# powersupply.net
KiCad netlist of a schematic drawn in Altium Designer
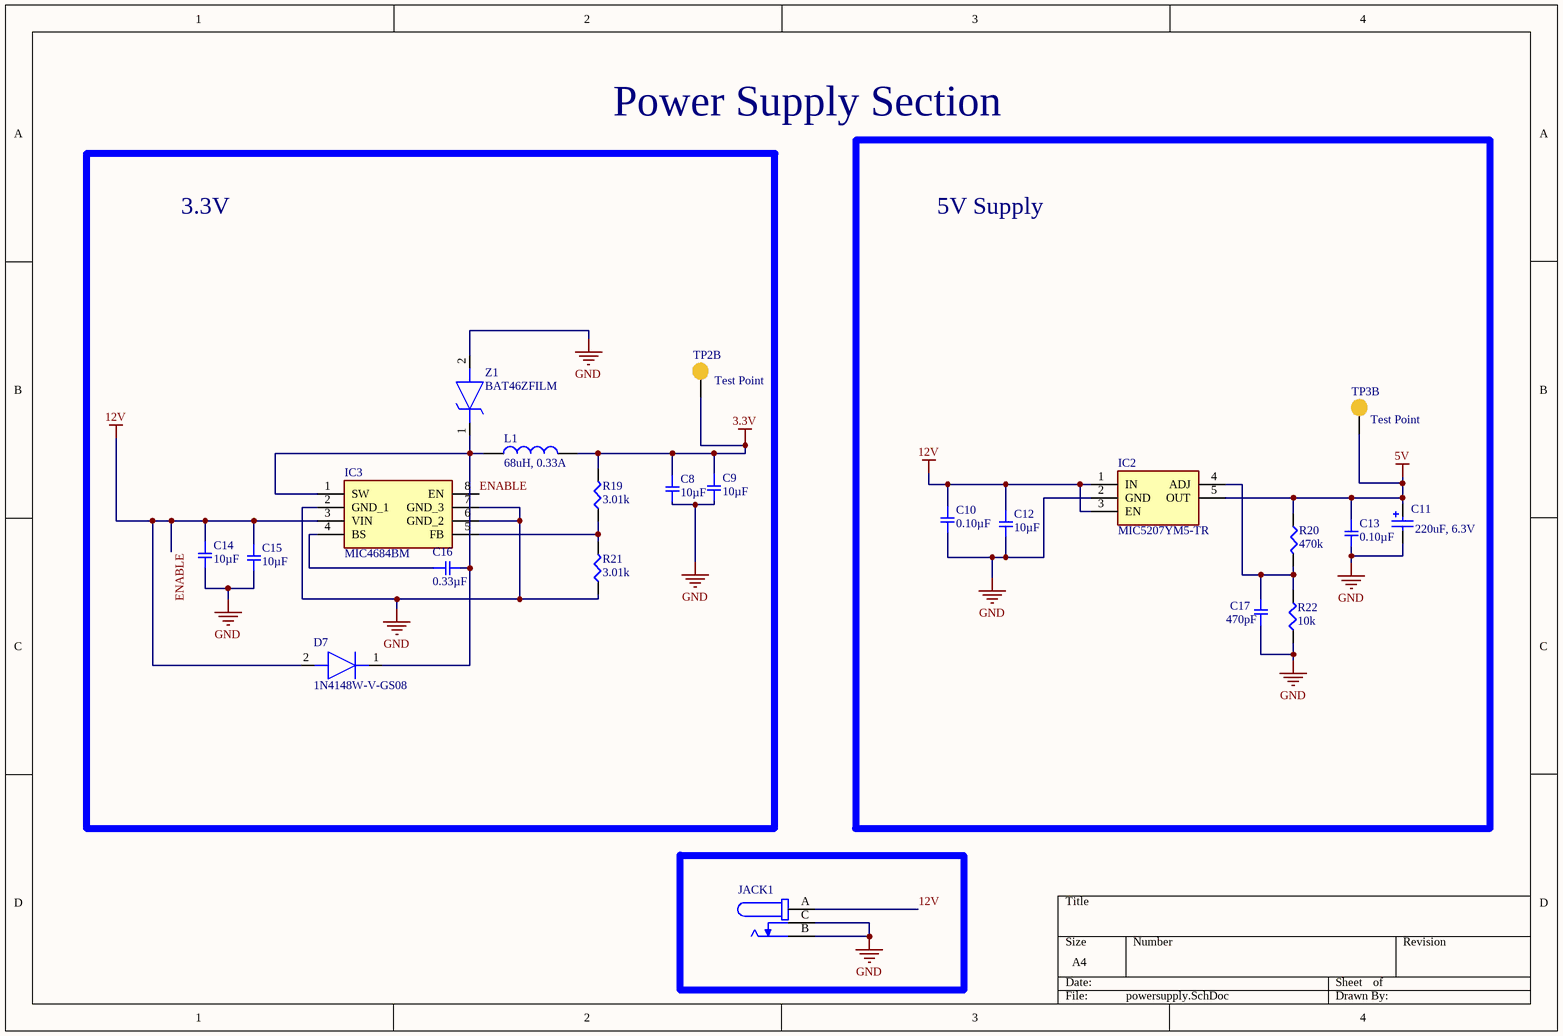
[diagram p0: powersupply.SchDoc]

(export (version "E")
  (design (tool "Eeschema 10.0.6"))
  (components
    (comp (ref "C8")
      (value "10µF")
      (footprint "SMD-0805C")
      (description "CAP CER 10UF 10V X7R 0805")
      (fields
        (field (name "DIGI-KEY PART NUMBER") "490-12646-1-ND")
        (field (name "PART NUMBER") "GCJ21BR71A106KE01L")
      )
      (libsource (lib "capacitor_murata_0805") (part "GCJ21BR71A106KE01L"))
    )
    (comp (ref "C9")
      (value "10µF")
      (footprint "SMD-0805C")
      (description "CAP CER 10UF 10V X7R 0805")
      (fields
        (field (name "DIGI-KEY PART NUMBER") "490-12646-1-ND")
        (field (name "PART NUMBER") "GCJ21BR71A106KE01L")
      )
      (libsource (lib "capacitor_murata_0805") (part "GCJ21BR71A106KE01L"))
    )
    (comp (ref "C10")
      (value "0.10µF")
      (footprint "SMD-0805C")
      (description "CAP CER 0.1UF 50V X7R 0805")
      (fields
        (field (name "DIGI-KEY PART NUMBER") "490-11955-1-ND")
        (field (name "PART NUMBER") "GCD21BR71H104KA01L")
      )
      (libsource (lib "capacitor_murata_0805") (part "GCD21BR71H104KA01L"))
    )
    (comp (ref "C11")
      (value "220uF, 6.3V")
      (footprint "WCAP-ASLI_6.3x5.5")
      (description "WCAP-ASLI SMT Aluminum Electrolytic Capacitors, D6.3mm x L5.5mm, 220uF, +/-20%, 6.3VDC")
      (fields (field (name "PART NUMBER") "865080143009") (field (name "PUBLISHER") "Wurth Elektronik"))
      (libsource (lib "SMD aluminum EL CAPS WCAP-ASLI_rev19a") (part "865080143009"))
    )
    (comp (ref "C12")
      (value "10µF")
      (footprint "SMD-0805C")
      (description "CAP CER 10UF 10V X7R 0805")
      (fields
        (field (name "DIGI-KEY PART NUMBER") "490-12646-1-ND")
        (field (name "PART NUMBER") "GCJ21BR71A106KE01L")
      )
      (libsource (lib "capacitor_murata_0805") (part "GCJ21BR71A106KE01L"))
    )
    (comp (ref "C13")
      (value "0.10µF")
      (footprint "SMD-0805C")
      (description "CAP CER 0.1UF 50V X7R 0805")
      (fields
        (field (name "DIGI-KEY PART NUMBER") "490-11955-1-ND")
        (field (name "PART NUMBER") "GCD21BR71H104KA01L")
      )
      (libsource (lib "capacitor_murata_0805") (part "GCD21BR71H104KA01L"))
    )
    (comp (ref "C14")
      (value "10µF")
      (footprint "SMD-0805C")
      (description "CAP CER 10UF 10V X7R 0805")
      (fields
        (field (name "DIGI-KEY PART NUMBER") "490-12646-1-ND")
        (field (name "PART NUMBER") "GCJ21BR71A106KE01L")
      )
      (libsource (lib "capacitor_murata_0805") (part "GCJ21BR71A106KE01L"))
    )
    (comp (ref "C15")
      (value "10µF")
      (footprint "SMD-0805C")
      (description "CAP CER 10UF 10V X7R 0805")
      (fields
        (field (name "DIGI-KEY PART NUMBER") "490-12646-1-ND")
        (field (name "PART NUMBER") "GCJ21BR71A106KE01L")
      )
      (libsource (lib "capacitor_murata_0805") (part "GCJ21BR71A106KE01L"))
    )
    (comp (ref "C16")
      (value "0.33µF")
      (footprint "SMD-0805C")
      (description "CAP CER 0.33UF 16V X7R 0805")
      (fields
        (field (name "DIGI-KEY PART NUMBER") "490-9752-1-ND")
        (field (name "PART NUMBER") "GRM21BR71C334KA01L")
      )
      (libsource (lib "capacitor_murata_0805") (part "GRM21BR71C334KA01L"))
    )
    (comp (ref "C17")
      (value "470pF")
      (footprint "SMD-0805C")
      (description "CAP CER 470PF 50V NP0 0805")
      (fields
        (field (name "DIGI-KEY PART NUMBER") "490-6056-1-ND")
        (field (name "PART NUMBER") "GCM2165C1H471JA16D")
      )
      (libsource (lib "capacitor_murata_0805") (part "GCM2165C1H471JA16D"))
    )
    (comp (ref "D7")
      (value "1N4148W-V-GS08")
      (footprint "SamacSys:1N4148WVGS08")
      (description "Diode")
      (fields (field (name "MOUSER PART NUMBER") "625-1N4148W-V"))
      (libsource (lib "*") (part "1N4148W-V-GS08"))
    )
    (comp (ref "IC2")
      (value "MIC5207YM5-TR")
      (footprint "SamacSys:SOT95P280X130-5N")
      (description "Integrated Circuit")
      (fields (field (name "MANUFACTURER_PART_NUMBER") "MIC5207"))
      (libsource (lib "*") (part "MIC5207"))
    )
    (comp (ref "IC3")
      (value "MIC4684BM")
      (footprint "SamacSys:SOIC127P602X173-8N")
      (description "Integrated Circuit")
      (libsource (lib "*") (part "MIC4684BM"))
    )
    (comp (ref "JACK1") (value "JACK") (footprint "JACK") (libsource (lib "Schlib1") (part "JACK")))
    (comp (ref "L1")
      (value "68uH, 0.33A")
      (footprint "WE-LQ_1812")
      (description "WE-LQ SMT Inductor, size 1812, 68uH, 0.33A")
      (fields
        (field (name "MANUFACTURER PART NUMBER") "744045680")
        (field (name "MANUFACTURER") "Wurth Elektronik")
      )
      (libsource (lib "SMD inductor 1WE-LQ_rev20a") (part "744045680"))
    )
    (comp (ref "R19")
      (value "3.01k")
      (footprint "SMD-0805-RES")
      (description "RES SMD 3.01K OHM 1% 1/8W 0805")
      (fields
        (field (name "PART NUMBER") "ERJ-6ENF3011V")
        (field (name "DIGI-KEY PART NUMBER") "P3.01KCCT-ND")
      )
      (libsource (lib "Panasonic_ERJ_0805") (part "ERJ-6ENF3011V"))
    )
    (comp (ref "R20")
      (value "470k")
      (footprint "SMD-0805-RES")
      (description "RES SMD 470K OHM 5% 1/2W 0805")
      (fields (field (name "PART NUMBER") "ERJ-P6WJ474V") (field (name "DIGI-KEY PART NUMBER") "P16986CT-ND"))
      (libsource (lib "Panasonic_ERJ_0805") (part "ERJ-P6WJ474V"))
    )
    (comp (ref "R21")
      (value "3.01k")
      (footprint "SMD-0805-RES")
      (description "RES SMD 3.01K OHM 1% 1/8W 0805")
      (fields
        (field (name "PART NUMBER") "ERJ-6ENF3011V")
        (field (name "DIGI-KEY PART NUMBER") "P3.01KCCT-ND")
      )
      (libsource (lib "Panasonic_ERJ_0805") (part "ERJ-6ENF3011V"))
    )
    (comp (ref "R22")
      (value "10k")
      (footprint "SMD-0805-RES")
      (description "RES SMD 10K OHM 5% 1/2W 0805")
      (fields (field (name "PART NUMBER") "ERJ-P6WJ103V") (field (name "DIGI-KEY PART NUMBER") "P16966CT-ND"))
      (libsource (lib "Panasonic_ERJ_0805") (part "ERJ-P6WJ103V"))
    )
    (comp (ref "TP2")
      (value "Test Point")
      (footprint "pad2")
      (description "Top Testpoint Pad")
      (libsource (lib "Schlib1") (part "pad2"))
    )
    (comp (ref "TP3")
      (value "Test Point")
      (footprint "pad2")
      (description "Top Testpoint Pad")
      (libsource (lib "Schlib1") (part "pad2"))
    )
    (comp (ref "Z1")
      (value "BAT46ZFILM")
      (footprint "SamacSys:STPS0560Z")
      (description "Zener Diode")
      (fields (field (name "MOUSER PART NUMBER") "511-BAT46ZFILM"))
      (libsource (lib "*") (part "BAT46ZFILM"))
    )
  )
  (nets
    (net (code "1") (name "3.3V") (class "Default")
      (node (ref "C8") (pin "1") (pinfunction "1_1") (pintype "passive"))
      (node (ref "C9") (pin "1") (pinfunction "1_1") (pintype "passive"))
      (node (ref "L1") (pin "2") (pinfunction "2_2") (pintype "passive"))
      (node (ref "R19") (pin "2") (pinfunction "2_2") (pintype "passive"))
      (node (ref "TP2") (pin "1") (pinfunction "1_1") (pintype "passive"))
    )
    (net (code "2") (name "5V") (class "Default")
      (node (ref "C11") (pin "2") (pinfunction "P_2") (pintype "passive"))
      (node (ref "C13") (pin "1") (pinfunction "1_1") (pintype "passive"))
      (node (ref "IC2") (pin "5") (pinfunction "OUT_5") (pintype "passive"))
      (node (ref "R20") (pin "1") (pinfunction "1_1") (pintype "passive"))
      (node (ref "TP3") (pin "1") (pinfunction "1_1") (pintype "passive"))
    )
    (net (code "3") (name "12V") (class "Default")
      (node (ref "C10") (pin "1") (pinfunction "1_1") (pintype "passive"))
      (node (ref "C12") (pin "1") (pinfunction "1_1") (pintype "passive"))
      (node (ref "C14") (pin "1") (pinfunction "1_1") (pintype "passive"))
      (node (ref "C15") (pin "1") (pinfunction "1_1") (pintype "passive"))
      (node (ref "D7") (pin "2") (pinfunction "A_2") (pintype "passive"))
      (node (ref "IC2") (pin "1") (pinfunction "IN_1") (pintype "passive"))
      (node (ref "IC2") (pin "3") (pinfunction "EN_3") (pintype "passive"))
      (node (ref "IC3") (pin "3") (pinfunction "VIN_3") (pintype "passive"))
      (node (ref "IC3") (pin "8") (pinfunction "EN_8") (pintype "passive"))
      (node (ref "JACK1") (pin "A") (pinfunction "A_A") (pintype "passive"))
    )
    (net (code "4") (name "GND") (class "Default")
      (node (ref "C10") (pin "2") (pinfunction "2_2") (pintype "passive"))
      (node (ref "C11") (pin "1") (pinfunction "N_1") (pintype "passive"))
      (node (ref "C12") (pin "2") (pinfunction "2_2") (pintype "passive"))
      (node (ref "C13") (pin "2") (pinfunction "2_2") (pintype "passive"))
      (node (ref "C14") (pin "2") (pinfunction "2_2") (pintype "passive"))
      (node (ref "C15") (pin "2") (pinfunction "2_2") (pintype "passive"))
      (node (ref "C17") (pin "1") (pinfunction "1_1") (pintype "passive"))
      (node (ref "C8") (pin "2") (pinfunction "2_2") (pintype "passive"))
      (node (ref "C9") (pin "2") (pinfunction "2_2") (pintype "passive"))
      (node (ref "IC2") (pin "2") (pinfunction "GND_2") (pintype "passive"))
      (node (ref "IC3") (pin "2") (pinfunction "GND_1_2") (pintype "passive"))
      (node (ref "IC3") (pin "6") (pinfunction "GND_2_6") (pintype "passive"))
      (node (ref "IC3") (pin "7") (pinfunction "GND_3_7") (pintype "passive"))
      (node (ref "JACK1") (pin "B") (pinfunction "B_B") (pintype "passive"))
      (node (ref "JACK1") (pin "C") (pinfunction "C_C") (pintype "passive"))
      (node (ref "R21") (pin "1") (pinfunction "1_1") (pintype "passive"))
      (node (ref "R22") (pin "1") (pinfunction "1_1") (pintype "passive"))
      (node (ref "Z1") (pin "2") (pinfunction "A_2") (pintype "passive"))
    )
    (net (code "5") (name "Net-(D7-K)") (class "Default")
      (node (ref "C16") (pin "2") (pinfunction "2_2") (pintype "passive"))
      (node (ref "D7") (pin "1") (pinfunction "K_1") (pintype "passive"))
      (node (ref "IC3") (pin "1") (pinfunction "SW_1") (pintype "passive"))
      (node (ref "L1") (pin "1") (pinfunction "1_1") (pintype "passive"))
      (node (ref "Z1") (pin "1") (pinfunction "K_1") (pintype "passive"))
    )
    (net (code "6") (name "Net-(IC2-ADJ)") (class "Default")
      (node (ref "C17") (pin "2") (pinfunction "2_2") (pintype "passive"))
      (node (ref "IC2") (pin "4") (pinfunction "ADJ_4") (pintype "passive"))
      (node (ref "R20") (pin "2") (pinfunction "2_2") (pintype "passive"))
      (node (ref "R22") (pin "2") (pinfunction "2_2") (pintype "passive"))
    )
    (net (code "7") (name "Net-(IC3-BS)") (class "Default")
      (node (ref "C16") (pin "1") (pinfunction "1_1") (pintype "passive"))
      (node (ref "IC3") (pin "4") (pinfunction "BS_4") (pintype "passive"))
    )
    (net (code "8") (name "Net-(IC3-FB)") (class "Default")
      (node (ref "IC3") (pin "5") (pinfunction "FB_5") (pintype "passive"))
      (node (ref "R19") (pin "1") (pinfunction "1_1") (pintype "passive"))
      (node (ref "R21") (pin "2") (pinfunction "2_2") (pintype "passive"))
    )
  )
)
